# team_throttle_control_draft_2.net
KiCad netlist of a schematic drawn in Altium Designer
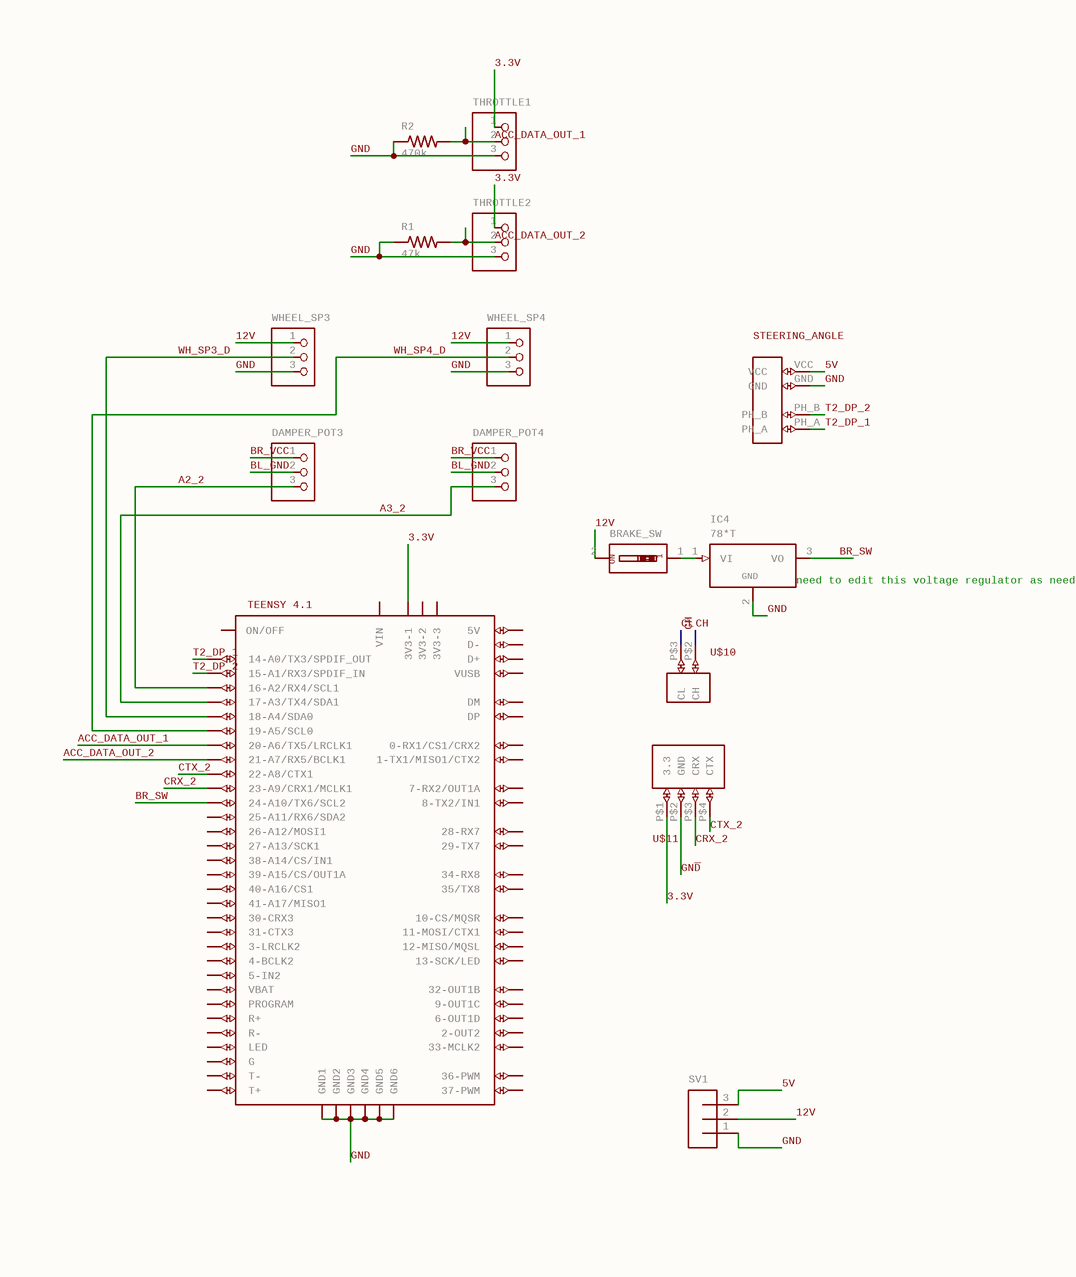
[diagram p0: team throttle control draft 2.SchDoc]

(export (version "E")
  (design (tool "Eeschema 10.0.6"))
  (components
    (comp (ref "BRAKE_SW")
      (value "SW_DIP-1")
      (footprint "EDG-01")
      (description "DIP SWITCH")
      (fields (field (name "1") "1") (field (name "ON") "ON"))
      (libsource (lib "special") (part "SW_DIP-1"))
    )
    (comp (ref "DAMPER_POT3")
      (value "PINHD-1X3CB")
      (footprint "1X03-CLEANBIG")
      (description "PIN HEADER")
      (libsource (lib "adafruit") (part "PINHD-1X3CB"))
    )
    (comp (ref "DAMPER_POT4")
      (value "PINHD-1X3CB")
      (footprint "1X03-CLEANBIG")
      (description "PIN HEADER")
      (libsource (lib "adafruit") (part "PINHD-1X3CB"))
    )
    (comp (ref "IC4")
      (value "78*T")
      (footprint "TO220H")
      (description "Positive VOLTAGE REGULATOR   Added bigger pads to the TO-92 package")
      (fields (field (name "GND") "GND"))
      (libsource (lib "adafruit") (part "78*T"))
    )
    (comp (ref "R1")
      (value "47k")
      (footprint "0204/7")
      (description "RESISTOR, American symbol")
      (libsource (lib "rcl") (part "R-US_0204/7"))
    )
    (comp (ref "R2")
      (value "470k")
      (footprint "0204/7")
      (description "RESISTOR, American symbol")
      (libsource (lib "rcl") (part "R-US_0204/7"))
    )
    (comp (ref "STEERING_ANGLE")
      (value "ROTARY_ENCODER")
      (footprint "ROTARY_ENCODER")
      (libsource (lib "F-E library custom components") (part "ROTARY_ENCODER"))
    )
    (comp (ref "SV1")
      (value "MA03-1")
      (footprint "MA03-1")
      (description "PIN HEADER")
      (fields (field (name "MF") "MF") (field (name "MPN") "MPN") (field (name "LIBRARYNAME") "con-lstb"))
      (libsource (lib "con-lstb") (part "MA03-1"))
    )
    (comp (ref "THROTTLE1")
      (value "PINHD-1X3")
      (footprint "1X03")
      (description "PIN HEADER")
      (libsource (lib "adafruit") (part "PINHD-1X3"))
    )
    (comp (ref "THROTTLE2")
      (value "PINHD-1X3")
      (footprint "1X03")
      (description "PIN HEADER")
      (libsource (lib "adafruit") (part "PINHD-1X3"))
    )
    (comp (ref "U$3")
      (value "TEENSY41")
      (footprint "TEENSY41")
      (fields (field (name "TEENSY4.1") "TEENSY 4.1"))
      (libsource (lib "teensy") (part "TEENSY41"))
    )
    (comp (ref "U$10")
      (value "CAN_BUS")
      (footprint "CAN_BUS")
      (libsource (lib "F-E library custom components") (part "CAN_BUS"))
    )
    (comp (ref "U$11")
      (value "CAN_TEE")
      (footprint "CAN_TEN")
      (libsource (lib "F-E library custom components") (part "CAN_TEE"))
    )
    (comp (ref "WHEEL_SP3")
      (value "PINHD-1X3")
      (footprint "1X03")
      (description "PIN HEADER")
      (libsource (lib "adafruit") (part "PINHD-1X3"))
    )
    (comp (ref "WHEEL_SP4")
      (value "PINHD-1X3")
      (footprint "1X03")
      (description "PIN HEADER")
      (libsource (lib "adafruit") (part "PINHD-1X3"))
    )
  )
  (nets
    (net (code "3") (name "/3.3V") (class "Default")
      (node (ref "THROTTLE1") (pin "1") (pinfunction "1_1") (pintype "passive"))
      (node (ref "THROTTLE2") (pin "1") (pinfunction "1_1") (pintype "passive"))
      (node (ref "U$11") (pin "P$1") (pinfunction "3.3_P$1") (pintype "bidirectional"))
      (node (ref "U$3") (pin "3V3-1") (pinfunction "3V3-1_3V3-1") (pintype "bidirectional"))
    )
    (net (code "4") (name "/5V") (class "Default")
      (node (ref "STEERING_ANGLE") (pin "VCC") (pinfunction "VCC_VCC") (pintype "bidirectional"))
      (node (ref "SV1") (pin "3") (pinfunction "3_3") (pintype "passive"))
    )
    (net (code "5") (name "/12V") (class "Default")
      (node (ref "BRAKE_SW") (pin "2") (pinfunction "2_2") (pintype "passive"))
      (node (ref "SV1") (pin "2") (pinfunction "2_2") (pintype "passive"))
      (node (ref "WHEEL_SP3") (pin "1") (pinfunction "1_1") (pintype "passive"))
      (node (ref "WHEEL_SP4") (pin "1") (pinfunction "1_1") (pintype "passive"))
    )
    (net (code "6") (name "/A2_2") (class "Default")
      (node (ref "DAMPER_POT3") (pin "3") (pinfunction "3_3") (pintype "passive"))
      (node (ref "U$3") (pin "16-A2/RX4/SCL1") (pinfunction "16-A2/RX4/SCL1_16-A2/RX4/SCL1") (pintype "bidirectional"))
    )
    (net (code "7") (name "/A3_2") (class "Default")
      (node (ref "DAMPER_POT4") (pin "3") (pinfunction "3_3") (pintype "passive"))
      (node (ref "U$3") (pin "17-A3/TX4/SDA1") (pinfunction "17-A3/TX4/SDA1_17-A3/TX4/SDA1") (pintype "bidirectional"))
    )
    (net (code "8") (name "/ACC_DATA_OUT_1") (class "Default")
      (node (ref "R2") (pin "2") (pinfunction "2_2") (pintype "passive"))
      (node (ref "THROTTLE1") (pin "2") (pinfunction "2_2") (pintype "passive"))
      (node (ref "U$3") (pin "20-A6/TX5/LRCLK1") (pinfunction "20-A6/TX5/LRCLK1_20-A6/TX5/LRCLK1") (pintype "bidirectional"))
    )
    (net (code "9") (name "/ACC_DATA_OUT_2") (class "Default")
      (node (ref "R1") (pin "2") (pinfunction "2_2") (pintype "passive"))
      (node (ref "THROTTLE2") (pin "2") (pinfunction "2_2") (pintype "passive"))
      (node (ref "U$3") (pin "21-A7/RX5/BCLK1") (pinfunction "21-A7/RX5/BCLK1_21-A7/RX5/BCLK1") (pintype "bidirectional"))
    )
    (net (code "10") (name "/BL_GND") (class "Default")
      (node (ref "DAMPER_POT3") (pin "2") (pinfunction "2_2") (pintype "passive"))
      (node (ref "DAMPER_POT4") (pin "2") (pinfunction "2_2") (pintype "passive"))
    )
    (net (code "11") (name "/BR_SW") (class "Default")
      (node (ref "IC4") (pin "3") (pinfunction "VO_3") (pintype "passive"))
      (node (ref "U$3") (pin "24-A10/TX6/SCL2") (pinfunction "24-A10/TX6/SCL2_24-A10/TX6/SCL2") (pintype "bidirectional"))
    )
    (net (code "12") (name "/BR_VCC") (class "Default")
      (node (ref "DAMPER_POT3") (pin "1") (pinfunction "1_1") (pintype "passive"))
      (node (ref "DAMPER_POT4") (pin "1") (pinfunction "1_1") (pintype "passive"))
    )
    (net (code "13") (name "/CRX_2") (class "Default")
      (node (ref "U$11") (pin "P$3") (pinfunction "CRX_P$3") (pintype "bidirectional"))
      (node (ref "U$3") (pin "23-A9/CRX1/MCLK1") (pinfunction "23-A9/CRX1/MCLK1_23-A9/CRX1/MCLK1") (pintype "bidirectional"))
    )
    (net (code "14") (name "/CTX_2") (class "Default")
      (node (ref "U$11") (pin "P$4") (pinfunction "CTX_P$4") (pintype "bidirectional"))
      (node (ref "U$3") (pin "22-A8/CTX1") (pinfunction "22-A8/CTX1_22-A8/CTX1") (pintype "bidirectional"))
    )
    (net (code "15") (name "/GND") (class "Default")
      (node (ref "IC4") (pin "2") (pinfunction "GND_2") (pintype "passive"))
      (node (ref "R1") (pin "1") (pinfunction "1_1") (pintype "passive"))
      (node (ref "R2") (pin "1") (pinfunction "1_1") (pintype "passive"))
      (node (ref "STEERING_ANGLE") (pin "GND") (pinfunction "GND_GND") (pintype "bidirectional"))
      (node (ref "SV1") (pin "1") (pinfunction "1_1") (pintype "passive"))
      (node (ref "THROTTLE1") (pin "3") (pinfunction "3_3") (pintype "passive"))
      (node (ref "THROTTLE2") (pin "3") (pinfunction "3_3") (pintype "passive"))
      (node (ref "U$3") (pin "GND1") (pinfunction "GND1_GND1") (pintype "bidirectional"))
      (node (ref "U$3") (pin "GND2") (pinfunction "GND2_GND2") (pintype "bidirectional"))
      (node (ref "U$3") (pin "GND3") (pinfunction "GND3_GND3") (pintype "bidirectional"))
      (node (ref "U$3") (pin "GND4") (pinfunction "GND4_GND4") (pintype "bidirectional"))
      (node (ref "U$3") (pin "GND5") (pinfunction "GND5_GND5") (pintype "bidirectional"))
      (node (ref "U$3") (pin "GND6") (pinfunction "GND6_GND6") (pintype "bidirectional"))
      (node (ref "WHEEL_SP3") (pin "3") (pinfunction "3_3") (pintype "passive"))
      (node (ref "WHEEL_SP4") (pin "3") (pinfunction "3_3") (pintype "passive"))
    )
    (net (code "16") (name "/GN~{D}") (class "Default")
      (node (ref "U$11") (pin "P$2") (pinfunction "GND_P$2") (pintype "bidirectional"))
    )
    (net (code "17") (name "/T2_DP_1") (class "Default")
      (node (ref "STEERING_ANGLE") (pin "PH_A") (pinfunction "PH_A_PH_A") (pintype "bidirectional"))
      (node (ref "U$3") (pin "14-A0/TX3/SPDIF_OUT") (pinfunction "14-A0/TX3/SPDIF_OUT_14-A0/TX3/SPDIF_OUT") (pintype "bidirectional"))
    )
    (net (code "18") (name "/T2_DP_2") (class "Default")
      (node (ref "STEERING_ANGLE") (pin "PH_B") (pinfunction "PH_B_PH_B") (pintype "bidirectional"))
      (node (ref "U$3") (pin "15-A1/RX3/SPDIF_IN") (pinfunction "15-A1/RX3/SPDIF_IN_15-A1/RX3/SPDIF_IN") (pintype "bidirectional"))
    )
    (net (code "19") (name "/WH_SP3_D") (class "Default")
      (node (ref "U$3") (pin "18-A4/SDA0") (pinfunction "18-A4/SDA0_18-A4/SDA0") (pintype "bidirectional"))
      (node (ref "WHEEL_SP3") (pin "2") (pinfunction "2_2") (pintype "passive"))
    )
    (net (code "20") (name "/WH_SP4_D") (class "Default")
      (node (ref "U$3") (pin "19-A5/SCL0") (pinfunction "19-A5/SCL0_19-A5/SCL0") (pintype "bidirectional"))
      (node (ref "WHEEL_SP4") (pin "2") (pinfunction "2_2") (pintype "passive"))
    )
    (net (code "21") (name "/{CH}") (class "Default")
      (node (ref "U$10") (pin "P$2") (pinfunction "CH_P$2") (pintype "bidirectional"))
    )
    (net (code "22") (name "/{CL}") (class "Default")
      (node (ref "U$10") (pin "P$3") (pinfunction "CL_P$3") (pintype "bidirectional"))
    )
    (net (code "23") (name "Net-(IC4-VI)") (class "Default")
      (node (ref "BRAKE_SW") (pin "1") (pinfunction "1_1") (pintype "passive"))
      (node (ref "IC4") (pin "1") (pinfunction "VI_1") (pintype "input"))
    )
    (net (code "24") (name "unconnected-(U$3-5V-Pad+5V)") (class "Default")
      (node (ref "U$3") (pin "+5V") (pinfunction "5V_+5V") (pintype "bidirectional"))
    )
    (net (code "25") (name "unconnected-(U$3-8-TX2{slash}IN1-Pad8-TX2{slash}IN2)") (class "Default")
      (node (ref "U$3") (pin "8-TX2/IN2") (pinfunction "8-TX2/IN1_8-TX2/IN2") (pintype "bidirectional"))
    )
    (net (code "26") (name "unconnected-(U$3-10-CS{slash}MQSR-Pad10-C~{S}MQSR)") (class "Default")
      (node (ref "U$3") (pin "10-C~{S}MQSR") (pinfunction "10-CS/MQSR_10-C~{S}MQSR") (pintype "bidirectional"))
    )
    (net (code "27") (name "unconnected-(U$3-35{slash}TX8-Pad35-TX8)") (class "Default")
      (node (ref "U$3") (pin "35-TX8") (pinfunction "35/TX8_35-TX8") (pintype "bidirectional"))
    )
    (net (code "28") (name "unconnected-(U$3-Pad0-RX1{slash}CS1{slash}CRX2)") (class "Default")
      (node (ref "U$3") (pin "0-RX1/CS1/CRX2") (pinfunction "0-RX1/CS1/CRX2_0-RX1/CS1/CRX2") (pintype "bidirectional"))
    )
    (net (code "29") (name "unconnected-(U$3-Pad1-TX1{slash}MISO1{slash}CTX2)") (class "Default")
      (node (ref "U$3") (pin "1-TX1/MISO1/CTX2") (pinfunction "1-TX1/MISO1/CTX2_1-TX1/MISO1/CTX2") (pintype "bidirectional"))
    )
    (net (code "30") (name "unconnected-(U$3-Pad2-OUT2)") (class "Default")
      (node (ref "U$3") (pin "2-OUT2") (pinfunction "2-OUT2_2-OUT2") (pintype "bidirectional"))
    )
    (net (code "31") (name "unconnected-(U$3-Pad3-LRCLK2)") (class "Default")
      (node (ref "U$3") (pin "3-LRCLK2") (pinfunction "3-LRCLK2_3-LRCLK2") (pintype "bidirectional"))
    )
    (net (code "32") (name "unconnected-(U$3-Pad3V3-2)") (class "Default")
      (node (ref "U$3") (pin "3V3-2") (pinfunction "3V3-2_3V3-2") (pintype "bidirectional"))
    )
    (net (code "33") (name "unconnected-(U$3-Pad3V3-3)") (class "Default")
      (node (ref "U$3") (pin "3V3-3") (pinfunction "3V3-3_3V3-3") (pintype "bidirectional"))
    )
    (net (code "34") (name "unconnected-(U$3-Pad4-BCLK2)") (class "Default")
      (node (ref "U$3") (pin "4-BCLK2") (pinfunction "4-BCLK2_4-BCLK2") (pintype "bidirectional"))
    )
    (net (code "35") (name "unconnected-(U$3-Pad5-IN2)") (class "Default")
      (node (ref "U$3") (pin "5-IN2") (pinfunction "5-IN2_5-IN2") (pintype "bidirectional"))
    )
    (net (code "36") (name "unconnected-(U$3-Pad6-OUT1D)") (class "Default")
      (node (ref "U$3") (pin "6-OUT1D") (pinfunction "6-OUT1D_6-OUT1D") (pintype "bidirectional"))
    )
    (net (code "37") (name "unconnected-(U$3-Pad7-RX2{slash}OUT1A)") (class "Default")
      (node (ref "U$3") (pin "7-RX2/OUT1A") (pinfunction "7-RX2/OUT1A_7-RX2/OUT1A") (pintype "bidirectional"))
    )
    (net (code "38") (name "unconnected-(U$3-Pad9-OUT1C)") (class "Default")
      (node (ref "U$3") (pin "9-OUT1C") (pinfunction "9-OUT1C_9-OUT1C") (pintype "bidirectional"))
    )
    (net (code "39") (name "unconnected-(U$3-Pad11-MOSI{slash}CTX1)") (class "Default")
      (node (ref "U$3") (pin "11-MOSI/CTX1") (pinfunction "11-MOSI/CTX1_11-MOSI/CTX1") (pintype "bidirectional"))
    )
    (net (code "40") (name "unconnected-(U$3-Pad12-MISO{slash}MQSL)") (class "Default")
      (node (ref "U$3") (pin "12-MISO/MQSL") (pinfunction "12-MISO/MQSL_12-MISO/MQSL") (pintype "bidirectional"))
    )
    (net (code "41") (name "unconnected-(U$3-Pad13-SCK{slash}LED)") (class "Default")
      (node (ref "U$3") (pin "13-SCK/LED") (pinfunction "13-SCK/LED_13-SCK/LED") (pintype "bidirectional"))
    )
    (net (code "42") (name "unconnected-(U$3-Pad25-A11{slash}RX6{slash}SDA2)") (class "Default")
      (node (ref "U$3") (pin "25-A11/RX6/SDA2") (pinfunction "25-A11/RX6/SDA2_25-A11/RX6/SDA2") (pintype "bidirectional"))
    )
    (net (code "43") (name "unconnected-(U$3-Pad26-A12{slash}MOSI1)") (class "Default")
      (node (ref "U$3") (pin "26-A12/MOSI1") (pinfunction "26-A12/MOSI1_26-A12/MOSI1") (pintype "bidirectional"))
    )
    (net (code "44") (name "unconnected-(U$3-Pad27-A13{slash}SCK1)") (class "Default")
      (node (ref "U$3") (pin "27-A13/SCK1") (pinfunction "27-A13/SCK1_27-A13/SCK1") (pintype "bidirectional"))
    )
    (net (code "45") (name "unconnected-(U$3-Pad28-RX7)") (class "Default")
      (node (ref "U$3") (pin "28-RX7") (pinfunction "28-RX7_28-RX7") (pintype "bidirectional"))
    )
    (net (code "46") (name "unconnected-(U$3-Pad29-TX7)") (class "Default")
      (node (ref "U$3") (pin "29-TX7") (pinfunction "29-TX7_29-TX7") (pintype "bidirectional"))
    )
    (net (code "47") (name "unconnected-(U$3-Pad30-CRX3)") (class "Default")
      (node (ref "U$3") (pin "30-CRX3") (pinfunction "30-CRX3_30-CRX3") (pintype "bidirectional"))
    )
    (net (code "48") (name "unconnected-(U$3-Pad31-CTX3)") (class "Default")
      (node (ref "U$3") (pin "31-CTX3") (pinfunction "31-CTX3_31-CTX3") (pintype "bidirectional"))
    )
    (net (code "49") (name "unconnected-(U$3-Pad32-OUT1B)") (class "Default")
      (node (ref "U$3") (pin "32-OUT1B") (pinfunction "32-OUT1B_32-OUT1B") (pintype "bidirectional"))
    )
    (net (code "50") (name "unconnected-(U$3-Pad33-MCLK2)") (class "Default")
      (node (ref "U$3") (pin "33-MCLK2") (pinfunction "33-MCLK2_33-MCLK2") (pintype "bidirectional"))
    )
    (net (code "51") (name "unconnected-(U$3-Pad34-RX8)") (class "Default")
      (node (ref "U$3") (pin "34-RX8") (pinfunction "34-RX8_34-RX8") (pintype "bidirectional"))
    )
    (net (code "52") (name "unconnected-(U$3-Pad36-PWM)") (class "Default")
      (node (ref "U$3") (pin "36-PWM") (pinfunction "36-PWM_36-PWM") (pintype "bidirectional"))
    )
    (net (code "53") (name "unconnected-(U$3-Pad37-PWM)") (class "Default")
      (node (ref "U$3") (pin "37-PWM") (pinfunction "37-PWM_37-PWM") (pintype "bidirectional"))
    )
    (net (code "54") (name "unconnected-(U$3-Pad38-A14{slash}CS{slash}IN1)") (class "Default")
      (node (ref "U$3") (pin "38-A14/CS/IN1") (pinfunction "38-A14/CS/IN1_38-A14/CS/IN1") (pintype "bidirectional"))
    )
    (net (code "55") (name "unconnected-(U$3-Pad39-A15{slash}CS{slash}OUT1A)") (class "Default")
      (node (ref "U$3") (pin "39-A15/CS/OUT1A") (pinfunction "39-A15/CS/OUT1A_39-A15/CS/OUT1A") (pintype "bidirectional"))
    )
    (net (code "56") (name "unconnected-(U$3-Pad40-A16{slash}CS1)") (class "Default")
      (node (ref "U$3") (pin "40-A16/CS1") (pinfunction "40-A16/CS1_40-A16/CS1") (pintype "bidirectional"))
    )
    (net (code "57") (name "unconnected-(U$3-Pad41-A17{slash}MISO1)") (class "Default")
      (node (ref "U$3") (pin "41-A17/MISO1") (pinfunction "41-A17/MISO1_41-A17/MISO1") (pintype "bidirectional"))
    )
    (net (code "58") (name "unconnected-(U$3-PadD+)") (class "Default")
      (node (ref "U$3") (pin "D+") (pinfunction "D+_D+") (pintype "bidirectional"))
    )
    (net (code "59") (name "unconnected-(U$3-PadD-)") (class "Default")
      (node (ref "U$3") (pin "D-") (pinfunction "D-_D-") (pintype "bidirectional"))
    )
    (net (code "60") (name "unconnected-(U$3-PadDM)") (class "Default")
      (node (ref "U$3") (pin "DM") (pinfunction "DM_DM") (pintype "bidirectional"))
    )
    (net (code "61") (name "unconnected-(U$3-PadDP)") (class "Default")
      (node (ref "U$3") (pin "DP") (pinfunction "DP_DP") (pintype "bidirectional"))
    )
    (net (code "62") (name "unconnected-(U$3-PadG)") (class "Default")
      (node (ref "U$3") (pin "G") (pinfunction "G_G") (pintype "bidirectional"))
    )
    (net (code "63") (name "unconnected-(U$3-PadLED)") (class "Default")
      (node (ref "U$3") (pin "LED") (pinfunction "LED_LED") (pintype "bidirectional"))
    )
    (net (code "64") (name "unconnected-(U$3-PadON{slash}OFF)") (class "Default")
      (node (ref "U$3") (pin "ON/OFF") (pinfunction "ON/OFF_ON/OFF") (pintype "bidirectional"))
    )
    (net (code "65") (name "unconnected-(U$3-PadPROGRAM)") (class "Default")
      (node (ref "U$3") (pin "PROGRAM") (pinfunction "PROGRAM_PROGRAM") (pintype "bidirectional"))
    )
    (net (code "66") (name "unconnected-(U$3-PadR+)") (class "Default")
      (node (ref "U$3") (pin "R+") (pinfunction "R+_R+") (pintype "bidirectional"))
    )
    (net (code "67") (name "unconnected-(U$3-PadR-)") (class "Default")
      (node (ref "U$3") (pin "R-") (pinfunction "R-_R-") (pintype "bidirectional"))
    )
    (net (code "68") (name "unconnected-(U$3-PadT+)") (class "Default")
      (node (ref "U$3") (pin "T+") (pinfunction "T+_T+") (pintype "bidirectional"))
    )
    (net (code "69") (name "unconnected-(U$3-PadT-)") (class "Default")
      (node (ref "U$3") (pin "T-") (pinfunction "T-_T-") (pintype "bidirectional"))
    )
    (net (code "70") (name "unconnected-(U$3-PadVBAT)") (class "Default")
      (node (ref "U$3") (pin "VBAT") (pinfunction "VBAT_VBAT") (pintype "bidirectional"))
    )
    (net (code "71") (name "unconnected-(U$3-PadVIN)") (class "Default")
      (node (ref "U$3") (pin "VIN") (pinfunction "VIN_VIN") (pintype "bidirectional"))
    )
    (net (code "72") (name "unconnected-(U$3-PadVUSB)") (class "Default")
      (node (ref "U$3") (pin "VUSB") (pinfunction "VUSB_VUSB") (pintype "bidirectional"))
    )
  )
)
